# CON_LCD_INDF.net
KiCad netlist of a schematic drawn in Altium Designer
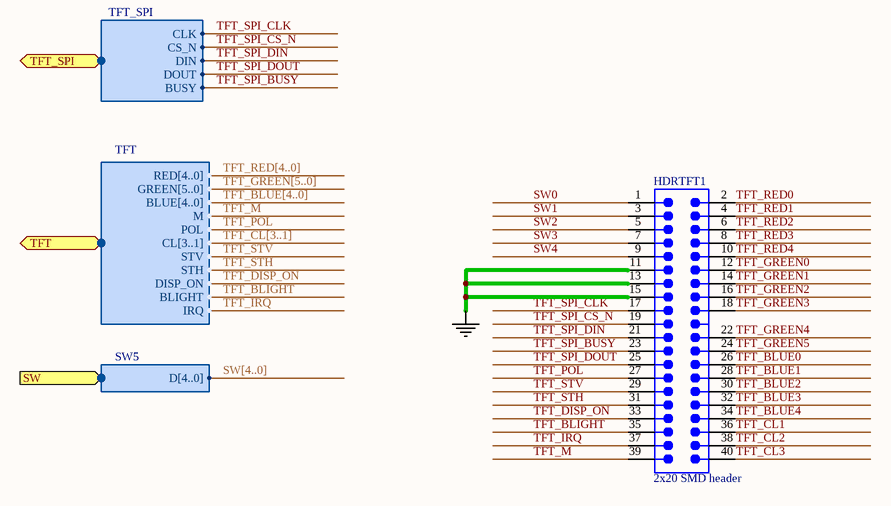
[diagram p0: CON_LCD_INDF.SchDoc]

(export (version "E")
  (design (tool "Eeschema 10.0.6"))
  (components
    (comp (ref "HDRTFT1")
      (value "2x20 SMD header")
      (footprint "HDR2X20_SMT")
      (description "Header IDC, 2 x 20 pin SMD, Vertical")
      (libsource (lib "AltiumDesignLibrary") (part "CON-IDC-2x20-M-STR"))
    )
  )
  (nets
    (net (code "4") (name "/SW0") (class "Default")
      (node (ref "HDRTFT1") (pin "1") (pinfunction "1_1") (pintype "passive"))
    )
    (net (code "5") (name "/SW1") (class "Default")
      (node (ref "HDRTFT1") (pin "3") (pinfunction "3_3") (pintype "passive"))
    )
    (net (code "6") (name "/SW2") (class "Default")
      (node (ref "HDRTFT1") (pin "5") (pinfunction "5_5") (pintype "passive"))
    )
    (net (code "7") (name "/SW3") (class "Default")
      (node (ref "HDRTFT1") (pin "7") (pinfunction "7_7") (pintype "passive"))
    )
    (net (code "8") (name "/SW4") (class "Default")
      (node (ref "HDRTFT1") (pin "9") (pinfunction "9_9") (pintype "passive"))
    )
    (net (code "10") (name "/TFT_BLIGHT") (class "Default")
      (node (ref "HDRTFT1") (pin "35") (pinfunction "35_35") (pintype "passive"))
    )
    (net (code "11") (name "/TFT_BLUE0") (class "Default")
      (node (ref "HDRTFT1") (pin "26") (pinfunction "26_26") (pintype "passive"))
    )
    (net (code "12") (name "/TFT_BLUE1") (class "Default")
      (node (ref "HDRTFT1") (pin "28") (pinfunction "28_28") (pintype "passive"))
    )
    (net (code "13") (name "/TFT_BLUE2") (class "Default")
      (node (ref "HDRTFT1") (pin "30") (pinfunction "30_30") (pintype "passive"))
    )
    (net (code "14") (name "/TFT_BLUE3") (class "Default")
      (node (ref "HDRTFT1") (pin "32") (pinfunction "32_32") (pintype "passive"))
    )
    (net (code "15") (name "/TFT_BLUE4") (class "Default")
      (node (ref "HDRTFT1") (pin "34") (pinfunction "34_34") (pintype "passive"))
    )
    (net (code "17") (name "/TFT_CL1") (class "Default")
      (node (ref "HDRTFT1") (pin "36") (pinfunction "36_36") (pintype "passive"))
    )
    (net (code "18") (name "/TFT_CL2") (class "Default")
      (node (ref "HDRTFT1") (pin "38") (pinfunction "38_38") (pintype "passive"))
    )
    (net (code "19") (name "/TFT_CL3") (class "Default")
      (node (ref "HDRTFT1") (pin "40") (pinfunction "40_40") (pintype "passive"))
    )
    (net (code "21") (name "/TFT_DISP_ON") (class "Default")
      (node (ref "HDRTFT1") (pin "33") (pinfunction "33_33") (pintype "passive"))
    )
    (net (code "22") (name "/TFT_GREEN0") (class "Default")
      (node (ref "HDRTFT1") (pin "12") (pinfunction "12_12") (pintype "passive"))
    )
    (net (code "23") (name "/TFT_GREEN1") (class "Default")
      (node (ref "HDRTFT1") (pin "14") (pinfunction "14_14") (pintype "passive"))
    )
    (net (code "24") (name "/TFT_GREEN2") (class "Default")
      (node (ref "HDRTFT1") (pin "16") (pinfunction "16_16") (pintype "passive"))
    )
    (net (code "25") (name "/TFT_GREEN3") (class "Default")
      (node (ref "HDRTFT1") (pin "18") (pinfunction "18_18") (pintype "passive"))
    )
    (net (code "26") (name "/TFT_GREEN4") (class "Default")
      (node (ref "HDRTFT1") (pin "22") (pinfunction "22_22") (pintype "passive"))
    )
    (net (code "27") (name "/TFT_GREEN5") (class "Default")
      (node (ref "HDRTFT1") (pin "24") (pinfunction "24_24") (pintype "passive"))
    )
    (net (code "29") (name "/TFT_IRQ") (class "Default")
      (node (ref "HDRTFT1") (pin "37") (pinfunction "37_37") (pintype "passive"))
    )
    (net (code "30") (name "/TFT_M") (class "Default")
      (node (ref "HDRTFT1") (pin "39") (pinfunction "39_39") (pintype "passive"))
    )
    (net (code "31") (name "/TFT_POL") (class "Default")
      (node (ref "HDRTFT1") (pin "27") (pinfunction "27_27") (pintype "passive"))
    )
    (net (code "32") (name "/TFT_RED0") (class "Default")
      (node (ref "HDRTFT1") (pin "2") (pinfunction "2_2") (pintype "passive"))
    )
    (net (code "33") (name "/TFT_RED1") (class "Default")
      (node (ref "HDRTFT1") (pin "4") (pinfunction "4_4") (pintype "passive"))
    )
    (net (code "34") (name "/TFT_RED2") (class "Default")
      (node (ref "HDRTFT1") (pin "6") (pinfunction "6_6") (pintype "passive"))
    )
    (net (code "35") (name "/TFT_RED3") (class "Default")
      (node (ref "HDRTFT1") (pin "8") (pinfunction "8_8") (pintype "passive"))
    )
    (net (code "36") (name "/TFT_RED4") (class "Default")
      (node (ref "HDRTFT1") (pin "10") (pinfunction "10_10") (pintype "passive"))
    )
    (net (code "37") (name "/TFT_SPI_BUSY") (class "Default")
      (node (ref "HDRTFT1") (pin "23") (pinfunction "23_23") (pintype "passive"))
    )
    (net (code "38") (name "/TFT_SPI_CLK") (class "Default")
      (node (ref "HDRTFT1") (pin "17") (pinfunction "17_17") (pintype "passive"))
    )
    (net (code "39") (name "/TFT_SPI_CS_N") (class "Default")
      (node (ref "HDRTFT1") (pin "19") (pinfunction "19_19") (pintype "passive"))
    )
    (net (code "40") (name "/TFT_SPI_DIN") (class "Default")
      (node (ref "HDRTFT1") (pin "21") (pinfunction "21_21") (pintype "passive"))
    )
    (net (code "41") (name "/TFT_SPI_DOUT") (class "Default")
      (node (ref "HDRTFT1") (pin "25") (pinfunction "25_25") (pintype "passive"))
    )
    (net (code "42") (name "/TFT_STH") (class "Default")
      (node (ref "HDRTFT1") (pin "31") (pinfunction "31_31") (pintype "passive"))
    )
    (net (code "43") (name "/TFT_STV") (class "Default")
      (node (ref "HDRTFT1") (pin "29") (pinfunction "29_29") (pintype "passive"))
    )
    (net (code "48") (name "GND") (class "Default")
      (node (ref "HDRTFT1") (pin "11") (pinfunction "11_11") (pintype "passive"))
      (node (ref "HDRTFT1") (pin "13") (pinfunction "13_13") (pintype "passive"))
      (node (ref "HDRTFT1") (pin "15") (pinfunction "15_15") (pintype "passive"))
    )
  )
)
